# PCB1_1_1.net
KiCad netlist of a schematic drawn in EAGLE
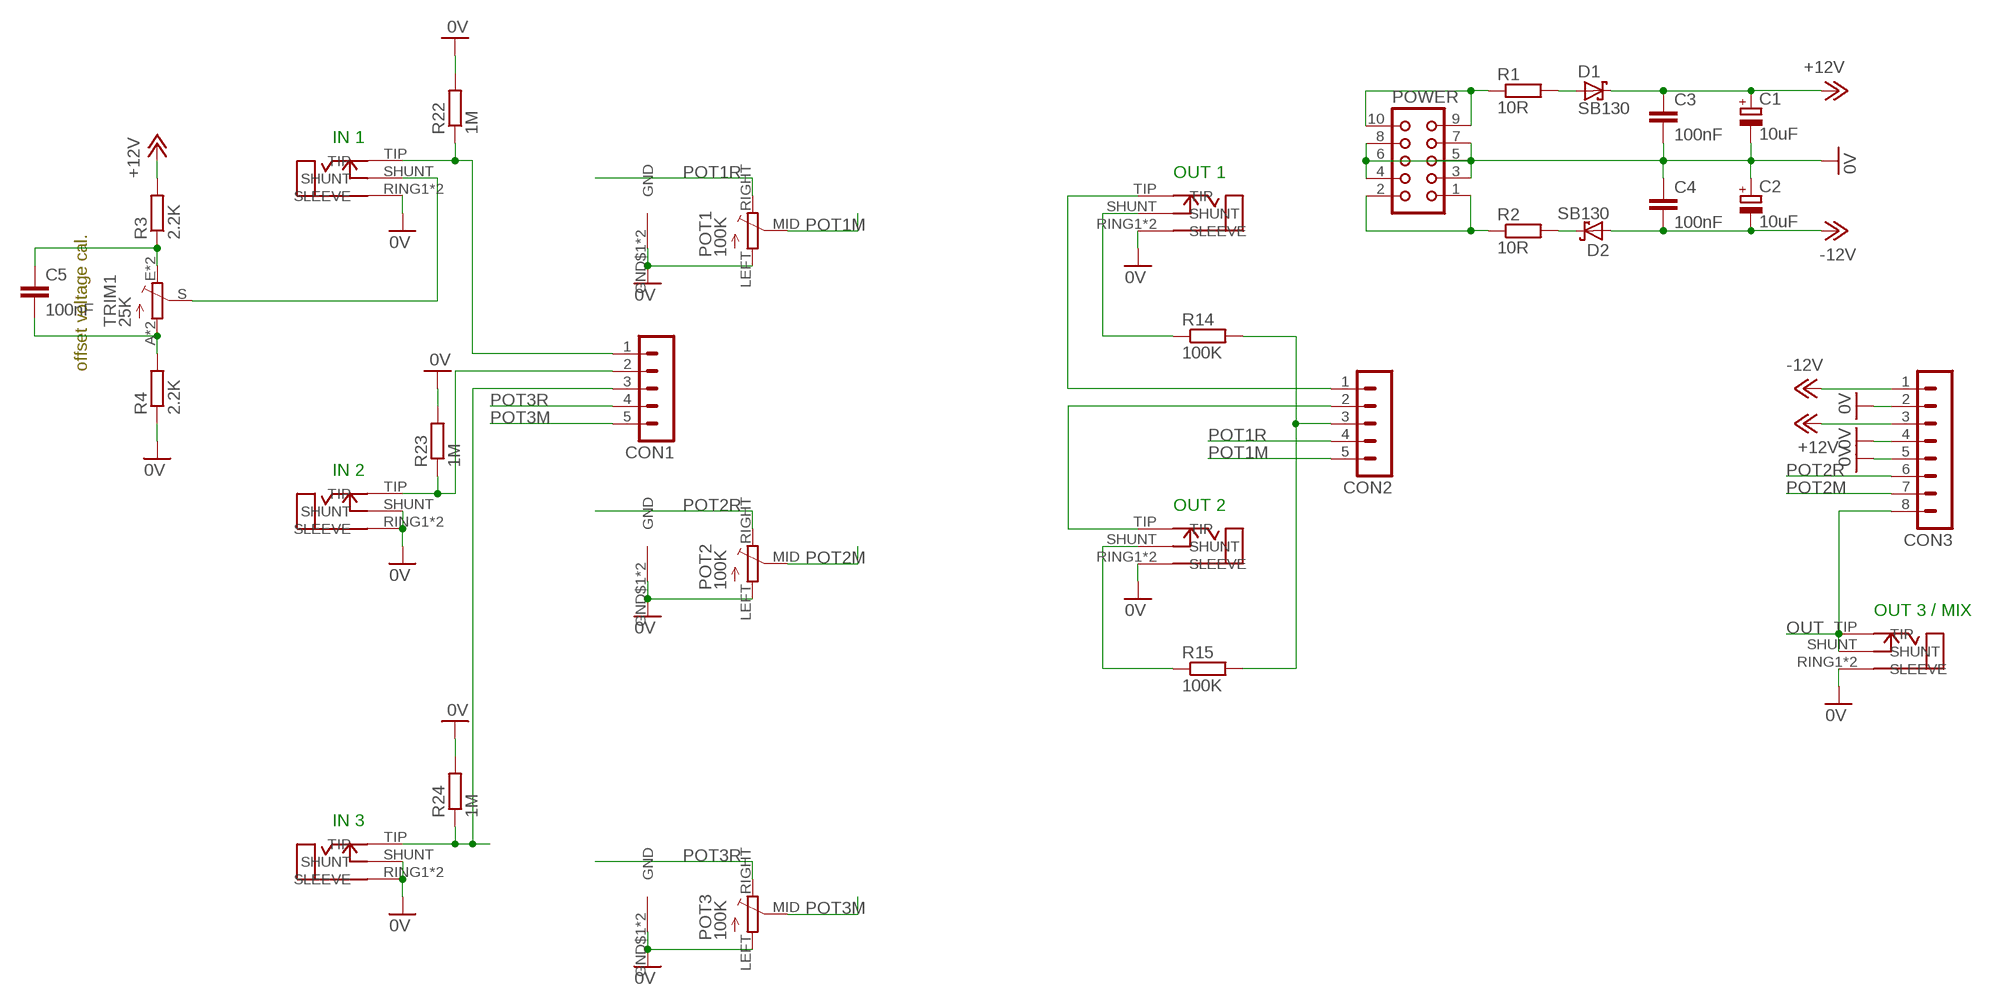
[diagram p0: schematic, sheet 1]

(export (version "E")
  (design (tool "Eeschema 10.0.6"))
  (components
    (comp (ref "C1")
      (value "10uF")
      (footprint "eagle-import:E2-5")
      (libsource (lib "eagle-import") (part "CPOL-EUE2-5"))
    )
    (comp (ref "C2")
      (value "10uF")
      (footprint "eagle-import:E2-5")
      (libsource (lib "eagle-import") (part "CPOL-EUE2-5"))
    )
    (comp (ref "C3")
      (value "100nF")
      (footprint "eagle-import:C025-024X044")
      (libsource (lib "eagle-import") (part "C-EU025-024X044"))
    )
    (comp (ref "C4")
      (value "100nF")
      (footprint "eagle-import:C025-024X044")
      (libsource (lib "eagle-import") (part "C-EU025-024X044"))
    )
    (comp (ref "C5")
      (value "100nF")
      (footprint "eagle-import:C025-024X044")
      (libsource (lib "eagle-import") (part "C-EU025-024X044"))
    )
    (comp (ref "CON1")
      (value "MA05-1")
      (footprint "eagle-import:MA05-1")
      (libsource (lib "eagle-import") (part "MA05-1"))
    )
    (comp (ref "CON2")
      (value "MA05-1")
      (footprint "eagle-import:MA05-1")
      (libsource (lib "eagle-import") (part "MA05-1"))
    )
    (comp (ref "CON3")
      (value "MA08-1")
      (footprint "eagle-import:MA08-1")
      (libsource (lib "eagle-import") (part "MA08-1"))
    )
    (comp (ref "D1")
      (value "SB130")
      (footprint "eagle-import:DO41-7")
      (libsource (lib "eagle-import") (part "SB130DO-204AL"))
    )
    (comp (ref "D2")
      (value "SB130")
      (footprint "eagle-import:DO41-7")
      (libsource (lib "eagle-import") (part "SB130DO-204AL"))
    )
    (comp (ref "IN1")
      (value "ERTHENVAR_3.5MM_JACK")
      (footprint "eagle-import:ERTHENVAR")
      (libsource (lib "eagle-import") (part "ERTHENVAR_3.5MM_JACK"))
    )
    (comp (ref "IN2")
      (value "ERTHENVAR_3.5MM_JACK")
      (footprint "eagle-import:ERTHENVAR")
      (libsource (lib "eagle-import") (part "ERTHENVAR_3.5MM_JACK"))
    )
    (comp (ref "IN3")
      (value "ERTHENVAR_3.5MM_JACK")
      (footprint "eagle-import:ERTHENVAR")
      (libsource (lib "eagle-import") (part "ERTHENVAR_3.5MM_JACK"))
    )
    (comp (ref "OUT1")
      (value "ERTHENVAR_3.5MM_JACK")
      (footprint "eagle-import:ERTHENVAR")
      (libsource (lib "eagle-import") (part "ERTHENVAR_3.5MM_JACK"))
    )
    (comp (ref "OUT2")
      (value "ERTHENVAR_3.5MM_JACK")
      (footprint "eagle-import:ERTHENVAR")
      (libsource (lib "eagle-import") (part "ERTHENVAR_3.5MM_JACK"))
    )
    (comp (ref "OUT3")
      (value "ERTHENVAR_3.5MM_JACK")
      (footprint "eagle-import:ERTHENVAR")
      (libsource (lib "eagle-import") (part "ERTHENVAR_3.5MM_JACK"))
    )
    (comp (ref "POT1")
      (value "100K")
      (footprint "eagle-import:POT-ALPHA9")
      (libsource (lib "eagle-import") (part "POT-ALPHA9"))
    )
    (comp (ref "POT2")
      (value "100K")
      (footprint "eagle-import:POT-ALPHA9")
      (libsource (lib "eagle-import") (part "POT-ALPHA9"))
    )
    (comp (ref "POT3")
      (value "100K")
      (footprint "eagle-import:POT-ALPHA9")
      (libsource (lib "eagle-import") (part "POT-ALPHA9"))
    )
    (comp (ref "POWER")
      (value "CON10L")
      (footprint "eagle-import:CON10L")
      (libsource (lib "eagle-import") (part "CON10L"))
    )
    (comp (ref "R1")
      (value "10R")
      (footprint "eagle-import:0207_9")
      (libsource (lib "eagle-import") (part "R-EU_0207/10"))
    )
    (comp (ref "R2")
      (value "10R")
      (footprint "eagle-import:0207_9")
      (libsource (lib "eagle-import") (part "R-EU_0207/10"))
    )
    (comp (ref "R3")
      (value "2.2K")
      (footprint "eagle-import:0207_9")
      (libsource (lib "eagle-import") (part "R-EU_0207/10"))
    )
    (comp (ref "R4")
      (value "2.2K")
      (footprint "eagle-import:0207_9")
      (libsource (lib "eagle-import") (part "R-EU_0207/10"))
    )
    (comp (ref "R14")
      (value "100K")
      (footprint "eagle-import:0207_9")
      (libsource (lib "eagle-import") (part "R-EU_0207/10"))
    )
    (comp (ref "R15")
      (value "100K")
      (footprint "eagle-import:0207_9")
      (libsource (lib "eagle-import") (part "R-EU_0207/10"))
    )
    (comp (ref "R22")
      (value "1M")
      (footprint "eagle-import:0207_9")
      (libsource (lib "eagle-import") (part "R-EU_0207/10"))
    )
    (comp (ref "R23")
      (value "1M")
      (footprint "eagle-import:0207_9")
      (libsource (lib "eagle-import") (part "R-EU_0207/10"))
    )
    (comp (ref "R24")
      (value "1M")
      (footprint "eagle-import:0207_9")
      (libsource (lib "eagle-import") (part "R-EU_0207/10"))
    )
    (comp (ref "TRIM1")
      (value "25K")
      (footprint "eagle-import:B25P")
      (libsource (lib "eagle-import") (part "TRIM_EU-B25P"))
    )
  )
  (nets
    (net (code "1") (name "+12V") (class "Default")
      (node (ref "C1") (pin "+") (pinfunction "+_+") (pintype "passive"))
      (node (ref "C3") (pin "1") (pinfunction "1_1") (pintype "passive"))
      (node (ref "CON3") (pin "3") (pinfunction "3_3") (pintype "passive"))
      (node (ref "D1") (pin "C") (pinfunction "C_C") (pintype "passive"))
      (node (ref "R3") (pin "2") (pinfunction "2_2") (pintype "passive"))
    )
    (net (code "2") (name "-12V") (class "Default")
      (node (ref "C2") (pin "-") (pinfunction "-_-") (pintype "passive"))
      (node (ref "C4") (pin "2") (pinfunction "2_2") (pintype "passive"))
      (node (ref "CON3") (pin "1") (pinfunction "1_1") (pintype "passive"))
      (node (ref "D2") (pin "A") (pinfunction "A_A") (pintype "passive"))
    )
    (net (code "3") (name "/OUT") (class "Default")
      (node (ref "CON3") (pin "8") (pinfunction "8_8") (pintype "passive"))
      (node (ref "OUT3") (pin "SHUNT") (pinfunction "SHUNT_SHUNT") (pintype "bidirectional"))
      (node (ref "OUT3") (pin "TIP") (pinfunction "TIP_TIP") (pintype "bidirectional"))
    )
    (net (code "4") (name "/POT1M") (class "Default")
      (node (ref "CON2") (pin "5") (pinfunction "5_5") (pintype "passive"))
      (node (ref "POT1") (pin "MID") (pinfunction "MID_MID") (pintype "passive"))
    )
    (net (code "5") (name "/POT1R") (class "Default")
      (node (ref "CON2") (pin "4") (pinfunction "4_4") (pintype "passive"))
      (node (ref "POT1") (pin "RIGHT") (pinfunction "RIGHT_RIGHT") (pintype "passive"))
    )
    (net (code "6") (name "/POT2M") (class "Default")
      (node (ref "CON3") (pin "7") (pinfunction "7_7") (pintype "passive"))
      (node (ref "POT2") (pin "MID") (pinfunction "MID_MID") (pintype "passive"))
    )
    (net (code "7") (name "/POT2R") (class "Default")
      (node (ref "CON3") (pin "6") (pinfunction "6_6") (pintype "passive"))
      (node (ref "POT2") (pin "RIGHT") (pinfunction "RIGHT_RIGHT") (pintype "passive"))
    )
    (net (code "8") (name "/POT3M") (class "Default")
      (node (ref "CON1") (pin "5") (pinfunction "5_5") (pintype "passive"))
      (node (ref "POT3") (pin "MID") (pinfunction "MID_MID") (pintype "passive"))
    )
    (net (code "9") (name "/POT3R") (class "Default")
      (node (ref "CON1") (pin "4") (pinfunction "4_4") (pintype "passive"))
      (node (ref "POT3") (pin "RIGHT") (pinfunction "RIGHT_RIGHT") (pintype "passive"))
    )
    (net (code "10") (name "0V") (class "Default")
      (node (ref "C1") (pin "-") (pinfunction "-_-") (pintype "passive"))
      (node (ref "C2") (pin "+") (pinfunction "+_+") (pintype "passive"))
      (node (ref "C3") (pin "2") (pinfunction "2_2") (pintype "passive"))
      (node (ref "C4") (pin "1") (pinfunction "1_1") (pintype "passive"))
      (node (ref "CON3") (pin "2") (pinfunction "2_2") (pintype "passive"))
      (node (ref "CON3") (pin "4") (pinfunction "4_4") (pintype "passive"))
      (node (ref "CON3") (pin "5") (pinfunction "5_5") (pintype "passive"))
      (node (ref "IN1") (pin "RING1") (pinfunction "SLEEVE_RING1") (pintype "bidirectional"))
      (node (ref "IN1") (pin "RING2") (pinfunction "SLEEVE_RING2") (pintype "bidirectional"))
      (node (ref "IN2") (pin "RING1") (pinfunction "SLEEVE_RING1") (pintype "bidirectional"))
      (node (ref "IN2") (pin "RING2") (pinfunction "SLEEVE_RING2") (pintype "bidirectional"))
      (node (ref "IN2") (pin "SHUNT") (pinfunction "SHUNT_SHUNT") (pintype "bidirectional"))
      (node (ref "IN3") (pin "RING1") (pinfunction "SLEEVE_RING1") (pintype "bidirectional"))
      (node (ref "IN3") (pin "RING2") (pinfunction "SLEEVE_RING2") (pintype "bidirectional"))
      (node (ref "IN3") (pin "SHUNT") (pinfunction "SHUNT_SHUNT") (pintype "bidirectional"))
      (node (ref "OUT1") (pin "RING1") (pinfunction "SLEEVE_RING1") (pintype "bidirectional"))
      (node (ref "OUT1") (pin "RING2") (pinfunction "SLEEVE_RING2") (pintype "bidirectional"))
      (node (ref "OUT2") (pin "RING1") (pinfunction "SLEEVE_RING1") (pintype "bidirectional"))
      (node (ref "OUT2") (pin "RING2") (pinfunction "SLEEVE_RING2") (pintype "bidirectional"))
      (node (ref "OUT3") (pin "RING1") (pinfunction "SLEEVE_RING1") (pintype "bidirectional"))
      (node (ref "OUT3") (pin "RING2") (pinfunction "SLEEVE_RING2") (pintype "bidirectional"))
      (node (ref "POT1") (pin "GND$1") (pinfunction "GND_GND$1") (pintype "bidirectional"))
      (node (ref "POT1") (pin "GND$2") (pinfunction "GND_GND$2") (pintype "bidirectional"))
      (node (ref "POT1") (pin "LEFT") (pinfunction "LEFT_LEFT") (pintype "passive"))
      (node (ref "POT2") (pin "GND$1") (pinfunction "GND_GND$1") (pintype "bidirectional"))
      (node (ref "POT2") (pin "GND$2") (pinfunction "GND_GND$2") (pintype "bidirectional"))
      (node (ref "POT2") (pin "LEFT") (pinfunction "LEFT_LEFT") (pintype "passive"))
      (node (ref "POT3") (pin "GND$1") (pinfunction "GND_GND$1") (pintype "bidirectional"))
      (node (ref "POT3") (pin "GND$2") (pinfunction "GND_GND$2") (pintype "bidirectional"))
      (node (ref "POT3") (pin "LEFT") (pinfunction "LEFT_LEFT") (pintype "passive"))
      (node (ref "POWER") (pin "3") (pinfunction "3_3") (pintype "passive"))
      (node (ref "POWER") (pin "4") (pinfunction "4_4") (pintype "passive"))
      (node (ref "POWER") (pin "5") (pinfunction "5_5") (pintype "passive"))
      (node (ref "POWER") (pin "6") (pinfunction "6_6") (pintype "passive"))
      (node (ref "POWER") (pin "7") (pinfunction "7_7") (pintype "passive"))
      (node (ref "POWER") (pin "8") (pinfunction "8_8") (pintype "passive"))
      (node (ref "R22") (pin "2") (pinfunction "2_2") (pintype "passive"))
      (node (ref "R23") (pin "2") (pinfunction "2_2") (pintype "passive"))
      (node (ref "R24") (pin "2") (pinfunction "2_2") (pintype "passive"))
      (node (ref "R4") (pin "1") (pinfunction "1_1") (pintype "passive"))
    )
    (net (code "11") (name "Net-(C5-Pad1)") (class "Default")
      (node (ref "C5") (pin "1") (pinfunction "1_1") (pintype "passive"))
      (node (ref "R3") (pin "1") (pinfunction "1_1") (pintype "passive"))
      (node (ref "TRIM1") (pin "E") (pinfunction "E_E") (pintype "passive"))
      (node (ref "TRIM1") (pin "EE") (pinfunction "E_EE") (pintype "passive"))
    )
    (net (code "12") (name "Net-(C5-Pad2)") (class "Default")
      (node (ref "C5") (pin "2") (pinfunction "2_2") (pintype "passive"))
      (node (ref "R4") (pin "2") (pinfunction "2_2") (pintype "passive"))
      (node (ref "TRIM1") (pin "A") (pinfunction "A_A") (pintype "passive"))
      (node (ref "TRIM1") (pin "AA") (pinfunction "A_AA") (pintype "passive"))
    )
    (net (code "13") (name "Net-(CON1-Pad1)") (class "Default")
      (node (ref "CON1") (pin "1") (pinfunction "1_1") (pintype "passive"))
      (node (ref "IN1") (pin "TIP") (pinfunction "TIP_TIP") (pintype "bidirectional"))
      (node (ref "R22") (pin "1") (pinfunction "1_1") (pintype "passive"))
    )
    (net (code "14") (name "Net-(CON1-Pad2)") (class "Default")
      (node (ref "CON1") (pin "2") (pinfunction "2_2") (pintype "passive"))
      (node (ref "IN2") (pin "TIP") (pinfunction "TIP_TIP") (pintype "bidirectional"))
      (node (ref "R23") (pin "1") (pinfunction "1_1") (pintype "passive"))
    )
    (net (code "15") (name "Net-(CON1-Pad3)") (class "Default")
      (node (ref "CON1") (pin "3") (pinfunction "3_3") (pintype "passive"))
      (node (ref "IN3") (pin "TIP") (pinfunction "TIP_TIP") (pintype "bidirectional"))
      (node (ref "R24") (pin "1") (pinfunction "1_1") (pintype "passive"))
    )
    (net (code "16") (name "Net-(CON2-Pad1)") (class "Default")
      (node (ref "CON2") (pin "1") (pinfunction "1_1") (pintype "passive"))
      (node (ref "OUT1") (pin "TIP") (pinfunction "TIP_TIP") (pintype "bidirectional"))
    )
    (net (code "17") (name "Net-(CON2-Pad2)") (class "Default")
      (node (ref "CON2") (pin "2") (pinfunction "2_2") (pintype "passive"))
      (node (ref "OUT2") (pin "TIP") (pinfunction "TIP_TIP") (pintype "bidirectional"))
    )
    (net (code "18") (name "Net-(CON2-Pad3)") (class "Default")
      (node (ref "CON2") (pin "3") (pinfunction "3_3") (pintype "passive"))
      (node (ref "R14") (pin "2") (pinfunction "2_2") (pintype "passive"))
      (node (ref "R15") (pin "2") (pinfunction "2_2") (pintype "passive"))
    )
    (net (code "19") (name "Net-(D1-PadA)") (class "Default")
      (node (ref "D1") (pin "A") (pinfunction "A_A") (pintype "passive"))
      (node (ref "R1") (pin "2") (pinfunction "2_2") (pintype "passive"))
    )
    (net (code "20") (name "Net-(D2-PadC)") (class "Default")
      (node (ref "D2") (pin "C") (pinfunction "C_C") (pintype "passive"))
      (node (ref "R2") (pin "2") (pinfunction "2_2") (pintype "passive"))
    )
    (net (code "21") (name "Net-(IN1-PadSHUNT)") (class "Default")
      (node (ref "IN1") (pin "SHUNT") (pinfunction "SHUNT_SHUNT") (pintype "bidirectional"))
      (node (ref "TRIM1") (pin "S") (pinfunction "S_S") (pintype "passive"))
    )
    (net (code "22") (name "Net-(OUT1-PadSHUNT)") (class "Default")
      (node (ref "OUT1") (pin "SHUNT") (pinfunction "SHUNT_SHUNT") (pintype "bidirectional"))
      (node (ref "R14") (pin "1") (pinfunction "1_1") (pintype "passive"))
    )
    (net (code "23") (name "Net-(OUT2-PadSHUNT)") (class "Default")
      (node (ref "OUT2") (pin "SHUNT") (pinfunction "SHUNT_SHUNT") (pintype "bidirectional"))
      (node (ref "R15") (pin "1") (pinfunction "1_1") (pintype "passive"))
    )
    (net (code "24") (name "Net-(POWER-Pad1)") (class "Default")
      (node (ref "POWER") (pin "1") (pinfunction "1_1") (pintype "passive"))
      (node (ref "POWER") (pin "2") (pinfunction "2_2") (pintype "passive"))
      (node (ref "R2") (pin "1") (pinfunction "1_1") (pintype "passive"))
    )
    (net (code "25") (name "Net-(POWER-Pad10)") (class "Default")
      (node (ref "POWER") (pin "10") (pinfunction "10_10") (pintype "passive"))
      (node (ref "POWER") (pin "9") (pinfunction "9_9") (pintype "passive"))
      (node (ref "R1") (pin "1") (pinfunction "1_1") (pintype "passive"))
    )
  )
)
